# EMS-ESP8266-12.net
KiCad netlist of a schematic drawn in EAGLE
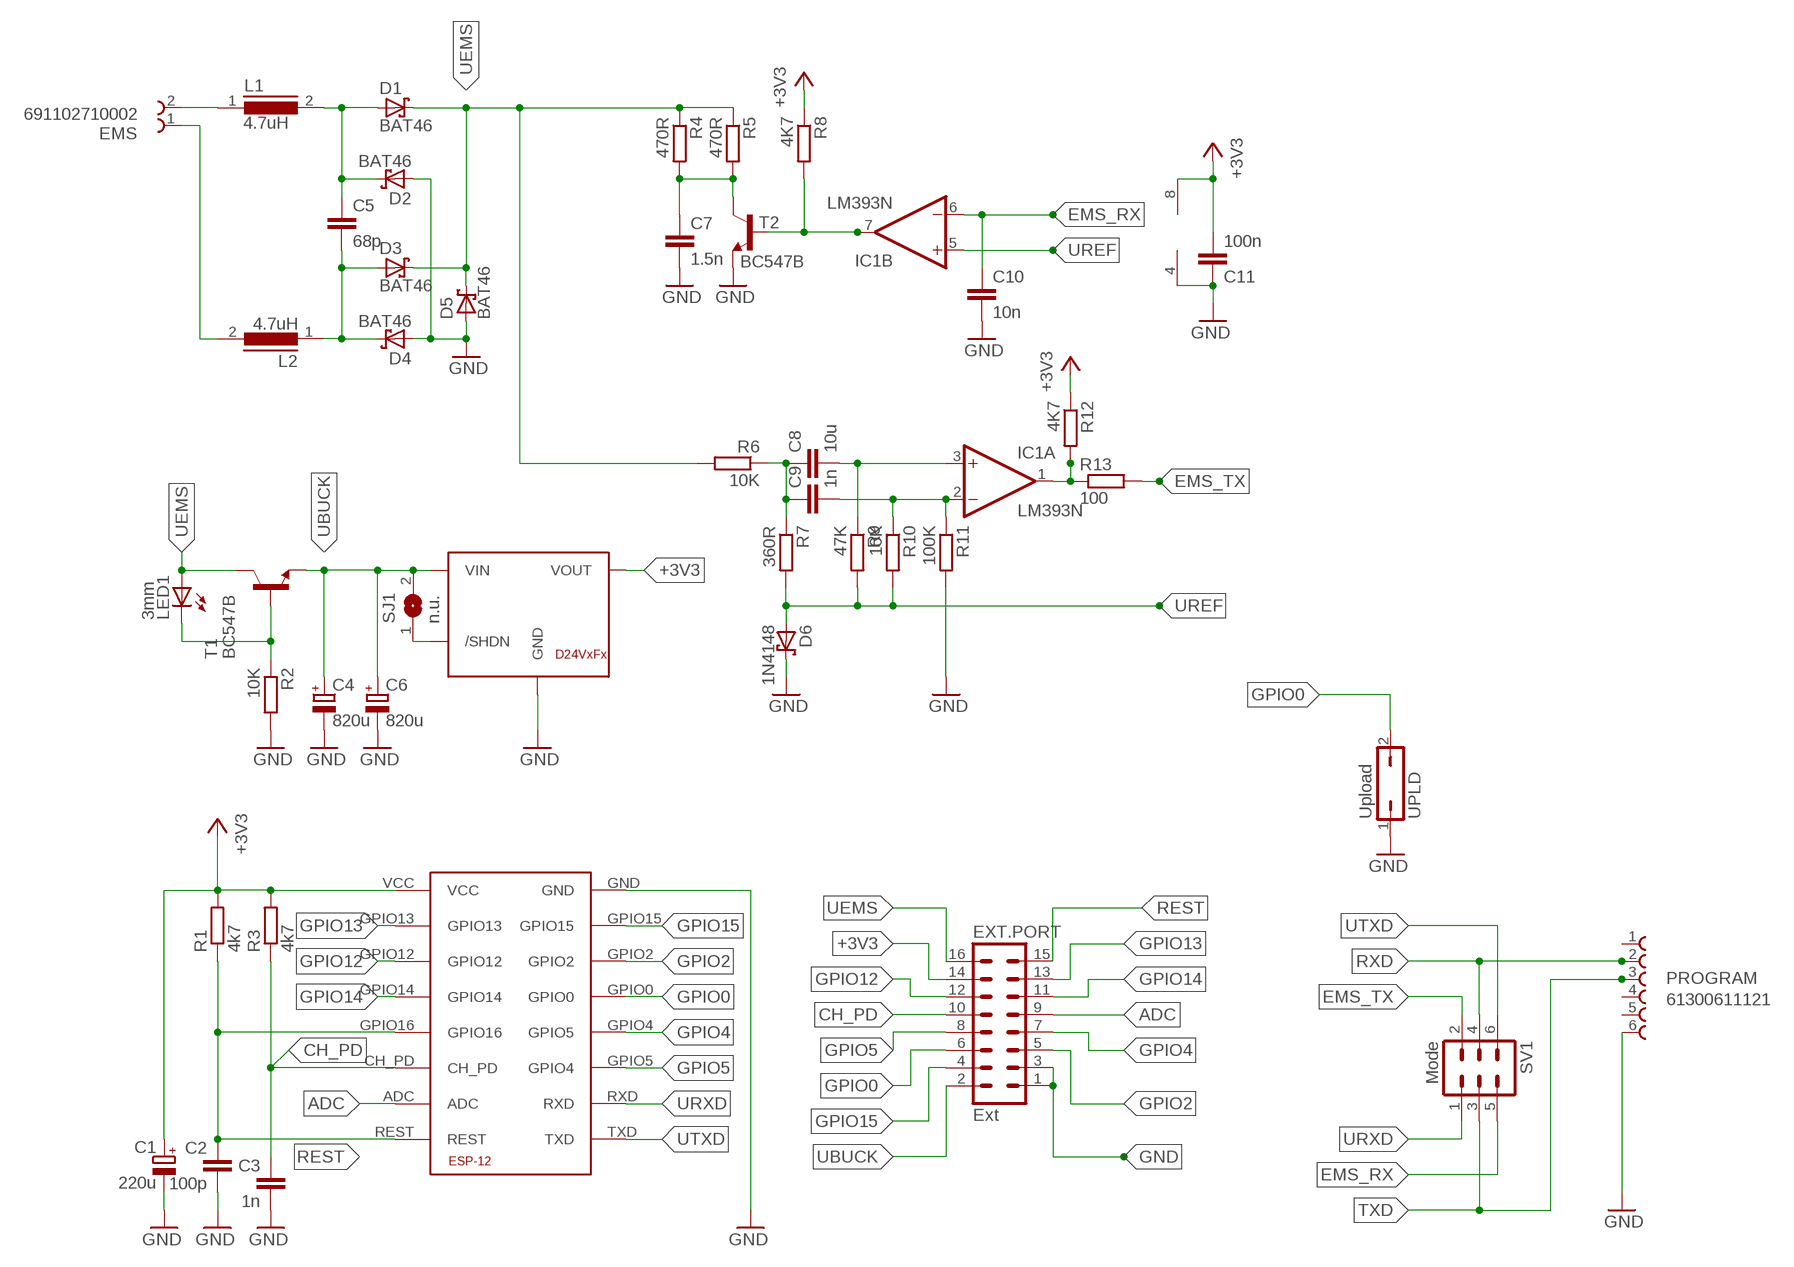
[diagram p0: schematic, sheet 1]

(export (version "E")
  (design (tool "Eeschema 10.0.6"))
  (components
    (comp (ref "C1")
      (value "220u")
      (footprint "eagle-import:UD-6,3X5,8_NICHICON")
      (libsource (lib "eagle-import") (part "CPOL-EUUD-6,3X8,8"))
    )
    (comp (ref "C2")
      (value "100p")
      (footprint "eagle-import:C2.5-2")
      (libsource (lib "eagle-import") (part "C2.5/2"))
    )
    (comp (ref "C3")
      (value "1n")
      (footprint "eagle-import:C2.5-2")
      (libsource (lib "eagle-import") (part "C2.5/2"))
    )
    (comp (ref "C4")
      (value "820u")
      (footprint "eagle-import:UD-10X10_NICHICON")
      (libsource (lib "eagle-import") (part "CPOL-EUUD-10X10"))
    )
    (comp (ref "C5")
      (value "68p")
      (footprint "eagle-import:C025-050X050")
      (libsource (lib "eagle-import") (part "C-EU025-050X050"))
    )
    (comp (ref "C6")
      (value "820u")
      (footprint "eagle-import:UD-10X10_NICHICON")
      (libsource (lib "eagle-import") (part "CPOL-EUUD-10X10"))
    )
    (comp (ref "C7")
      (value "1.5n")
      (footprint "eagle-import:C2.5-2")
      (libsource (lib "eagle-import") (part "C2.5/2"))
    )
    (comp (ref "C8")
      (value "10u")
      (footprint "eagle-import:C5B11")
      (libsource (lib "eagle-import") (part "C5/11"))
    )
    (comp (ref "C9")
      (value "1n")
      (footprint "eagle-import:C2.5-2")
      (libsource (lib "eagle-import") (part "C2.5/2"))
    )
    (comp (ref "C10")
      (value "10n")
      (footprint "eagle-import:C2.5-2")
      (libsource (lib "eagle-import") (part "C2.5/2"))
    )
    (comp (ref "C11")
      (value "100n")
      (footprint "eagle-import:C2.5-2")
      (libsource (lib "eagle-import") (part "C2.5/2"))
    )
    (comp (ref "D1")
      (value "BAT46")
      (footprint "eagle-import:DO35-7")
      (libsource (lib "eagle-import") (part "SCHOTTKY-DIODEDO35-7"))
    )
    (comp (ref "D2")
      (value "BAT46")
      (footprint "eagle-import:DO35-7")
      (libsource (lib "eagle-import") (part "SCHOTTKY-DIODEDO35-7"))
    )
    (comp (ref "D3")
      (value "BAT46")
      (footprint "eagle-import:DO35-7")
      (libsource (lib "eagle-import") (part "SCHOTTKY-DIODEDO35-7"))
    )
    (comp (ref "D4")
      (value "BAT46")
      (footprint "eagle-import:DO35-7")
      (libsource (lib "eagle-import") (part "SCHOTTKY-DIODEDO35-7"))
    )
    (comp (ref "D5")
      (value "BAT46")
      (footprint "eagle-import:DO35-7")
      (libsource (lib "eagle-import") (part "SCHOTTKY-DIODEDO35-7"))
    )
    (comp (ref "D6")
      (value "1N4148")
      (footprint "eagle-import:DO35-7")
      (libsource (lib "eagle-import") (part "SCHOTTKY-DIODEDO35-7"))
    )
    (comp (ref "EMS")
      (value "691102710002")
      (footprint "eagle-import:691102710002")
      (libsource (lib "eagle-import") (part "691102710002"))
    )
    (comp (ref "ESP1")
      (value "ESP-12ESP-12")
      (footprint "eagle-import:ESP-12")
      (libsource (lib "eagle-import") (part "ESP-12ESP-12"))
    )
    (comp (ref "EXT.PORT")
      (value "Ext")
      (footprint "eagle-import:MA08-2")
      (libsource (lib "eagle-import") (part "MA08-2"))
    )
    (comp (ref "IC1")
      (value "LM393N")
      (footprint "eagle-import:DIL08")
      (fields (field (name "REICHELT") "LM 393 DIP"))
      (libsource (lib "eagle-import") (part "LM393N"))
    )
    (comp (ref "L1")
      (value "4.7uH")
      (footprint "eagle-import:MICC12")
      (libsource (lib "eagle-import") (part "MICC12"))
    )
    (comp (ref "L2")
      (value "4.7uH")
      (footprint "eagle-import:MICC12")
      (libsource (lib "eagle-import") (part "MICC12"))
    )
    (comp (ref "LED1")
      (value "3mm")
      (footprint "eagle-import:LED3MM")
      (libsource (lib "eagle-import") (part "LED3MM"))
    )
    (comp (ref "MOD1")
      (value "D24V3F3")
      (footprint "eagle-import:D24VXFX")
      (libsource (lib "eagle-import") (part "D24VXFX"))
    )
    (comp (ref "PROGRAM")
      (value "61300611121")
      (footprint "eagle-import:61300611121")
      (libsource (lib "eagle-import") (part "61300611121"))
    )
    (comp (ref "R1")
      (value "4k7")
      (footprint "eagle-import:0204_7")
      (libsource (lib "eagle-import") (part "R-EU_0204/7"))
    )
    (comp (ref "R2")
      (value "10K")
      (footprint "eagle-import:0204_7")
      (libsource (lib "eagle-import") (part "R-EU_0204/7"))
    )
    (comp (ref "R3")
      (value "4k7")
      (footprint "eagle-import:0204_7")
      (libsource (lib "eagle-import") (part "R-EU_0204/7"))
    )
    (comp (ref "R4")
      (value "470R")
      (footprint "eagle-import:0204_7")
      (libsource (lib "eagle-import") (part "R-EU_0204/7"))
    )
    (comp (ref "R5")
      (value "470R")
      (footprint "eagle-import:0204_7")
      (libsource (lib "eagle-import") (part "R-EU_0204/7"))
    )
    (comp (ref "R6")
      (value "10K")
      (footprint "eagle-import:0204_7")
      (libsource (lib "eagle-import") (part "R-EU_0204/7"))
    )
    (comp (ref "R7")
      (value "360R")
      (footprint "eagle-import:0204_7")
      (libsource (lib "eagle-import") (part "R-EU_0204/7"))
    )
    (comp (ref "R8")
      (value "4K7")
      (footprint "eagle-import:0204_7")
      (libsource (lib "eagle-import") (part "R-EU_0204/7"))
    )
    (comp (ref "R9")
      (value "47K")
      (footprint "eagle-import:0204_7")
      (libsource (lib "eagle-import") (part "R-EU_0204/7"))
    )
    (comp (ref "R10")
      (value "10K")
      (footprint "eagle-import:0204_7")
      (libsource (lib "eagle-import") (part "R-EU_0204/7"))
    )
    (comp (ref "R11")
      (value "100K")
      (footprint "eagle-import:0204_7")
      (libsource (lib "eagle-import") (part "R-EU_0204/7"))
    )
    (comp (ref "R12")
      (value "4K7")
      (footprint "eagle-import:0204_7")
      (libsource (lib "eagle-import") (part "R-EU_0204/7"))
    )
    (comp (ref "R13")
      (value "100")
      (footprint "eagle-import:0204_7")
      (libsource (lib "eagle-import") (part "R-EU_0204/7"))
    )
    (comp (ref "SJ1")
      (value "n.u.")
      (footprint "eagle-import:SJ")
      (libsource (lib "eagle-import") (part "SJ"))
    )
    (comp (ref "SV1")
      (value "Mode")
      (footprint "eagle-import:MA03-2")
      (libsource (lib "eagle-import") (part "MA03-2"))
    )
    (comp (ref "T1")
      (value "BC547B")
      (footprint "eagle-import:TO92-EBC")
      (libsource (lib "eagle-import") (part "-NPN-TO92-EBC"))
    )
    (comp (ref "T2")
      (value "BC547B")
      (footprint "eagle-import:TO92-EBC")
      (libsource (lib "eagle-import") (part "-NPN-TO92-EBC"))
    )
    (comp (ref "UPLD")
      (value "Upload")
      (footprint "eagle-import:JP1")
      (libsource (lib "eagle-import") (part "JP1Q"))
    )
  )
  (nets
    (net (code "1") (name "+3V3") (class "Default")
      (node (ref "C1") (pin "+") (pinfunction "+_+") (pintype "passive"))
      (node (ref "C11") (pin "2") (pinfunction "2_2") (pintype "passive"))
      (node (ref "ESP1") (pin "VCC") (pinfunction "VCC_VCC") (pintype "bidirectional"))
      (node (ref "EXT.PORT") (pin "14") (pinfunction "14_14") (pintype "passive"))
      (node (ref "IC1") (pin "8") (pinfunction "V+_8") (pintype "power_in"))
      (node (ref "MOD1") (pin "VOUT") (pinfunction "VOUT_VOUT") (pintype "power_in"))
      (node (ref "R1") (pin "2") (pinfunction "2_2") (pintype "passive"))
      (node (ref "R12") (pin "1") (pinfunction "1_1") (pintype "passive"))
      (node (ref "R3") (pin "2") (pinfunction "2_2") (pintype "passive"))
      (node (ref "R8") (pin "1") (pinfunction "1_1") (pintype "passive"))
    )
    (net (code "2") (name "ADC") (class "Default")
      (node (ref "ESP1") (pin "ADC") (pinfunction "ADC_ADC") (pintype "bidirectional"))
      (node (ref "EXT.PORT") (pin "9") (pinfunction "9_9") (pintype "passive"))
    )
    (net (code "3") (name "CH_PD") (class "Default")
      (node (ref "C3") (pin "1") (pinfunction "1_1") (pintype "passive"))
      (node (ref "ESP1") (pin "CH_PD") (pinfunction "CH_PD_CH_PD") (pintype "bidirectional"))
      (node (ref "EXT.PORT") (pin "10") (pinfunction "10_10") (pintype "passive"))
      (node (ref "R3") (pin "1") (pinfunction "1_1") (pintype "passive"))
    )
    (net (code "4") (name "EMS_RX") (class "Default")
      (node (ref "C10") (pin "1") (pinfunction "1_1") (pintype "passive"))
      (node (ref "IC1") (pin "6") (pinfunction "-IN_6") (pintype "input"))
      (node (ref "SV1") (pin "5") (pinfunction "5_5") (pintype "passive"))
    )
    (net (code "5") (name "EMS_TX") (class "Default")
      (node (ref "R13") (pin "2") (pinfunction "2_2") (pintype "passive"))
      (node (ref "SV1") (pin "2") (pinfunction "2_2") (pintype "passive"))
    )
    (net (code "6") (name "GND") (class "Default")
      (node (ref "C1") (pin "-") (pinfunction "-_-") (pintype "passive"))
      (node (ref "C10") (pin "2") (pinfunction "2_2") (pintype "passive"))
      (node (ref "C11") (pin "1") (pinfunction "1_1") (pintype "passive"))
      (node (ref "C2") (pin "2") (pinfunction "2_2") (pintype "passive"))
      (node (ref "C3") (pin "2") (pinfunction "2_2") (pintype "passive"))
      (node (ref "C4") (pin "-") (pinfunction "-_-") (pintype "passive"))
      (node (ref "C6") (pin "-") (pinfunction "-_-") (pintype "passive"))
      (node (ref "C7") (pin "2") (pinfunction "2_2") (pintype "passive"))
      (node (ref "D2") (pin "A") (pinfunction "A_A") (pintype "passive"))
      (node (ref "D4") (pin "A") (pinfunction "A_A") (pintype "passive"))
      (node (ref "D5") (pin "A") (pinfunction "A_A") (pintype "passive"))
      (node (ref "D6") (pin "C") (pinfunction "C_C") (pintype "passive"))
      (node (ref "ESP1") (pin "GND") (pinfunction "GND_GND") (pintype "bidirectional"))
      (node (ref "EXT.PORT") (pin "1") (pinfunction "1_1") (pintype "passive"))
      (node (ref "EXT.PORT") (pin "3") (pinfunction "3_3") (pintype "passive"))
      (node (ref "IC1") (pin "4") (pinfunction "V-_4") (pintype "power_in"))
      (node (ref "MOD1") (pin "GND") (pinfunction "GND_GND") (pintype "power_in"))
      (node (ref "PROGRAM") (pin "6") (pinfunction "6_6") (pintype "passive"))
      (node (ref "R11") (pin "2") (pinfunction "2_2") (pintype "passive"))
      (node (ref "R2") (pin "2") (pinfunction "2_2") (pintype "passive"))
      (node (ref "T2") (pin "E") (pinfunction "E_E") (pintype "passive"))
      (node (ref "UPLD") (pin "1") (pinfunction "1_1") (pintype "passive"))
    )
    (net (code "7") (name "GPIO0") (class "Default")
      (node (ref "ESP1") (pin "GPIO0") (pinfunction "GPIO0_GPIO0") (pintype "bidirectional"))
      (node (ref "EXT.PORT") (pin "6") (pinfunction "6_6") (pintype "passive"))
      (node (ref "UPLD") (pin "2") (pinfunction "2_2") (pintype "passive"))
    )
    (net (code "8") (name "GPIO2") (class "Default")
      (node (ref "ESP1") (pin "GPIO2") (pinfunction "GPIO2_GPIO2") (pintype "bidirectional"))
      (node (ref "EXT.PORT") (pin "5") (pinfunction "5_5") (pintype "passive"))
    )
    (net (code "9") (name "GPIO4") (class "Default")
      (node (ref "ESP1") (pin "GPIO4") (pinfunction "GPIO5_GPIO4") (pintype "bidirectional"))
      (node (ref "EXT.PORT") (pin "7") (pinfunction "7_7") (pintype "passive"))
    )
    (net (code "10") (name "GPIO5") (class "Default")
      (node (ref "ESP1") (pin "GPIO5") (pinfunction "GPIO4_GPIO5") (pintype "bidirectional"))
      (node (ref "EXT.PORT") (pin "8") (pinfunction "8_8") (pintype "passive"))
    )
    (net (code "11") (name "GPIO12") (class "Default")
      (node (ref "ESP1") (pin "GPIO12") (pinfunction "GPIO12_GPIO12") (pintype "bidirectional"))
      (node (ref "EXT.PORT") (pin "12") (pinfunction "12_12") (pintype "passive"))
    )
    (net (code "12") (name "GPIO13") (class "Default")
      (node (ref "ESP1") (pin "GPIO13") (pinfunction "GPIO13_GPIO13") (pintype "bidirectional"))
      (node (ref "EXT.PORT") (pin "13") (pinfunction "13_13") (pintype "passive"))
    )
    (net (code "13") (name "GPIO14") (class "Default")
      (node (ref "ESP1") (pin "GPIO14") (pinfunction "GPIO14_GPIO14") (pintype "bidirectional"))
      (node (ref "EXT.PORT") (pin "11") (pinfunction "11_11") (pintype "passive"))
    )
    (net (code "14") (name "GPIO15") (class "Default")
      (node (ref "ESP1") (pin "GPIO15") (pinfunction "GPIO15_GPIO15") (pintype "bidirectional"))
      (node (ref "EXT.PORT") (pin "4") (pinfunction "4_4") (pintype "passive"))
    )
    (net (code "15") (name "Net-(C5-Pad1)") (class "Default")
      (node (ref "C5") (pin "1") (pinfunction "1_1") (pintype "passive"))
      (node (ref "D1") (pin "A") (pinfunction "A_A") (pintype "passive"))
      (node (ref "D2") (pin "C") (pinfunction "C_C") (pintype "passive"))
      (node (ref "L1") (pin "2") (pinfunction "2_2") (pintype "passive"))
    )
    (net (code "16") (name "Net-(C5-Pad2)") (class "Default")
      (node (ref "C5") (pin "2") (pinfunction "2_2") (pintype "passive"))
      (node (ref "D3") (pin "A") (pinfunction "A_A") (pintype "passive"))
      (node (ref "D4") (pin "C") (pinfunction "C_C") (pintype "passive"))
      (node (ref "L2") (pin "1") (pinfunction "1_1") (pintype "passive"))
    )
    (net (code "17") (name "Net-(C7-Pad1)") (class "Default")
      (node (ref "C7") (pin "1") (pinfunction "1_1") (pintype "passive"))
      (node (ref "R4") (pin "2") (pinfunction "2_2") (pintype "passive"))
      (node (ref "R5") (pin "2") (pinfunction "2_2") (pintype "passive"))
      (node (ref "T2") (pin "C") (pinfunction "C_C") (pintype "passive"))
    )
    (net (code "18") (name "Net-(C8-Pad1)") (class "Default")
      (node (ref "C8") (pin "1") (pinfunction "1_1") (pintype "passive"))
      (node (ref "C9") (pin "1") (pinfunction "1_1") (pintype "passive"))
      (node (ref "R6") (pin "1") (pinfunction "1_1") (pintype "passive"))
      (node (ref "R7") (pin "1") (pinfunction "1_1") (pintype "passive"))
    )
    (net (code "19") (name "Net-(EMS-Pad1)") (class "Default")
      (node (ref "EMS") (pin "1") (pinfunction "1_1") (pintype "passive"))
      (node (ref "L2") (pin "2") (pinfunction "2_2") (pintype "passive"))
    )
    (net (code "20") (name "Net-(EMS-Pad2)") (class "Default")
      (node (ref "EMS") (pin "2") (pinfunction "2_2") (pintype "passive"))
      (node (ref "L1") (pin "1") (pinfunction "1_1") (pintype "passive"))
    )
    (net (code "21") (name "Net-(IC1A-+IN)") (class "Default")
      (node (ref "C8") (pin "2") (pinfunction "2_2") (pintype "passive"))
      (node (ref "IC1") (pin "3") (pinfunction "+IN_3") (pintype "input"))
      (node (ref "R9") (pin "1") (pinfunction "1_1") (pintype "passive"))
    )
    (net (code "22") (name "Net-(IC1A--IN)") (class "Default")
      (node (ref "C9") (pin "2") (pinfunction "2_2") (pintype "passive"))
      (node (ref "IC1") (pin "2") (pinfunction "-IN_2") (pintype "input"))
      (node (ref "R10") (pin "1") (pinfunction "1_1") (pintype "passive"))
      (node (ref "R11") (pin "1") (pinfunction "1_1") (pintype "passive"))
    )
    (net (code "23") (name "Net-(IC1A-OUT)") (class "Default")
      (node (ref "IC1") (pin "1") (pinfunction "OUT_1") (pintype "output"))
      (node (ref "R12") (pin "2") (pinfunction "2_2") (pintype "passive"))
      (node (ref "R13") (pin "1") (pinfunction "1_1") (pintype "passive"))
    )
    (net (code "24") (name "Net-(IC1B-OUT)") (class "Default")
      (node (ref "IC1") (pin "7") (pinfunction "OUT_7") (pintype "output"))
      (node (ref "R8") (pin "2") (pinfunction "2_2") (pintype "passive"))
      (node (ref "T2") (pin "B") (pinfunction "B_B") (pintype "passive"))
    )
    (net (code "25") (name "Net-(LED1-C)") (class "Default")
      (node (ref "LED1") (pin "K") (pinfunction "C_K") (pintype "passive"))
      (node (ref "R2") (pin "1") (pinfunction "1_1") (pintype "passive"))
      (node (ref "T1") (pin "B") (pinfunction "B_B") (pintype "passive"))
    )
    (net (code "26") (name "Net-(MOD1-Pad{slash}SHDN)") (class "Default")
      (node (ref "MOD1") (pin "/SHDN") (pinfunction "/SHDN_/SHDN") (pintype "input"))
      (node (ref "SJ1") (pin "1") (pinfunction "1_1") (pintype "passive"))
    )
    (net (code "27") (name "REST") (class "Default")
      (node (ref "C2") (pin "1") (pinfunction "1_1") (pintype "passive"))
      (node (ref "ESP1") (pin "GPIO16") (pinfunction "GPIO16_GPIO16") (pintype "bidirectional"))
      (node (ref "ESP1") (pin "REST") (pinfunction "REST_REST") (pintype "bidirectional"))
      (node (ref "EXT.PORT") (pin "15") (pinfunction "15_15") (pintype "passive"))
      (node (ref "R1") (pin "1") (pinfunction "1_1") (pintype "passive"))
    )
    (net (code "28") (name "RXD") (class "Default")
      (node (ref "PROGRAM") (pin "2") (pinfunction "2_2") (pintype "passive"))
      (node (ref "SV1") (pin "4") (pinfunction "4_4") (pintype "passive"))
    )
    (net (code "29") (name "TXD") (class "Default")
      (node (ref "PROGRAM") (pin "3") (pinfunction "3_3") (pintype "passive"))
      (node (ref "SV1") (pin "3") (pinfunction "3_3") (pintype "passive"))
    )
    (net (code "30") (name "UBUCK") (class "Default")
      (node (ref "C4") (pin "+") (pinfunction "+_+") (pintype "passive"))
      (node (ref "C6") (pin "+") (pinfunction "+_+") (pintype "passive"))
      (node (ref "EXT.PORT") (pin "2") (pinfunction "2_2") (pintype "passive"))
      (node (ref "MOD1") (pin "VIN") (pinfunction "VIN_VIN") (pintype "power_in"))
      (node (ref "SJ1") (pin "2") (pinfunction "2_2") (pintype "passive"))
      (node (ref "T1") (pin "E") (pinfunction "E_E") (pintype "passive"))
    )
    (net (code "31") (name "UEMS") (class "Default")
      (node (ref "D1") (pin "C") (pinfunction "C_C") (pintype "passive"))
      (node (ref "D3") (pin "C") (pinfunction "C_C") (pintype "passive"))
      (node (ref "D5") (pin "C") (pinfunction "C_C") (pintype "passive"))
      (node (ref "EXT.PORT") (pin "16") (pinfunction "16_16") (pintype "passive"))
      (node (ref "LED1") (pin "A") (pinfunction "A_A") (pintype "passive"))
      (node (ref "R4") (pin "1") (pinfunction "1_1") (pintype "passive"))
      (node (ref "R5") (pin "1") (pinfunction "1_1") (pintype "passive"))
      (node (ref "R6") (pin "2") (pinfunction "2_2") (pintype "passive"))
      (node (ref "T1") (pin "C") (pinfunction "C_C") (pintype "passive"))
    )
    (net (code "32") (name "UREF") (class "Default")
      (node (ref "D6") (pin "A") (pinfunction "A_A") (pintype "passive"))
      (node (ref "IC1") (pin "5") (pinfunction "+IN_5") (pintype "input"))
      (node (ref "R10") (pin "2") (pinfunction "2_2") (pintype "passive"))
      (node (ref "R7") (pin "2") (pinfunction "2_2") (pintype "passive"))
      (node (ref "R9") (pin "2") (pinfunction "2_2") (pintype "passive"))
    )
    (net (code "33") (name "URXD") (class "Default")
      (node (ref "ESP1") (pin "RXD") (pinfunction "RXD_RXD") (pintype "bidirectional"))
      (node (ref "SV1") (pin "1") (pinfunction "1_1") (pintype "passive"))
    )
    (net (code "34") (name "UTXD") (class "Default")
      (node (ref "ESP1") (pin "TXD") (pinfunction "TXD_TXD") (pintype "bidirectional"))
      (node (ref "SV1") (pin "6") (pinfunction "6_6") (pintype "passive"))
    )
    (net (code "35") (name "unconnected-(PROGRAM-Pad1)") (class "Default")
      (node (ref "PROGRAM") (pin "1") (pinfunction "1_1") (pintype "passive"))
    )
    (net (code "36") (name "unconnected-(PROGRAM-Pad4)") (class "Default")
      (node (ref "PROGRAM") (pin "4") (pinfunction "4_4") (pintype "passive"))
    )
    (net (code "37") (name "unconnected-(PROGRAM-Pad5)") (class "Default")
      (node (ref "PROGRAM") (pin "5") (pinfunction "5_5") (pintype "passive"))
    )
  )
)
